# Sheet7.net
KiCad netlist of a schematic drawn in Altium Designer
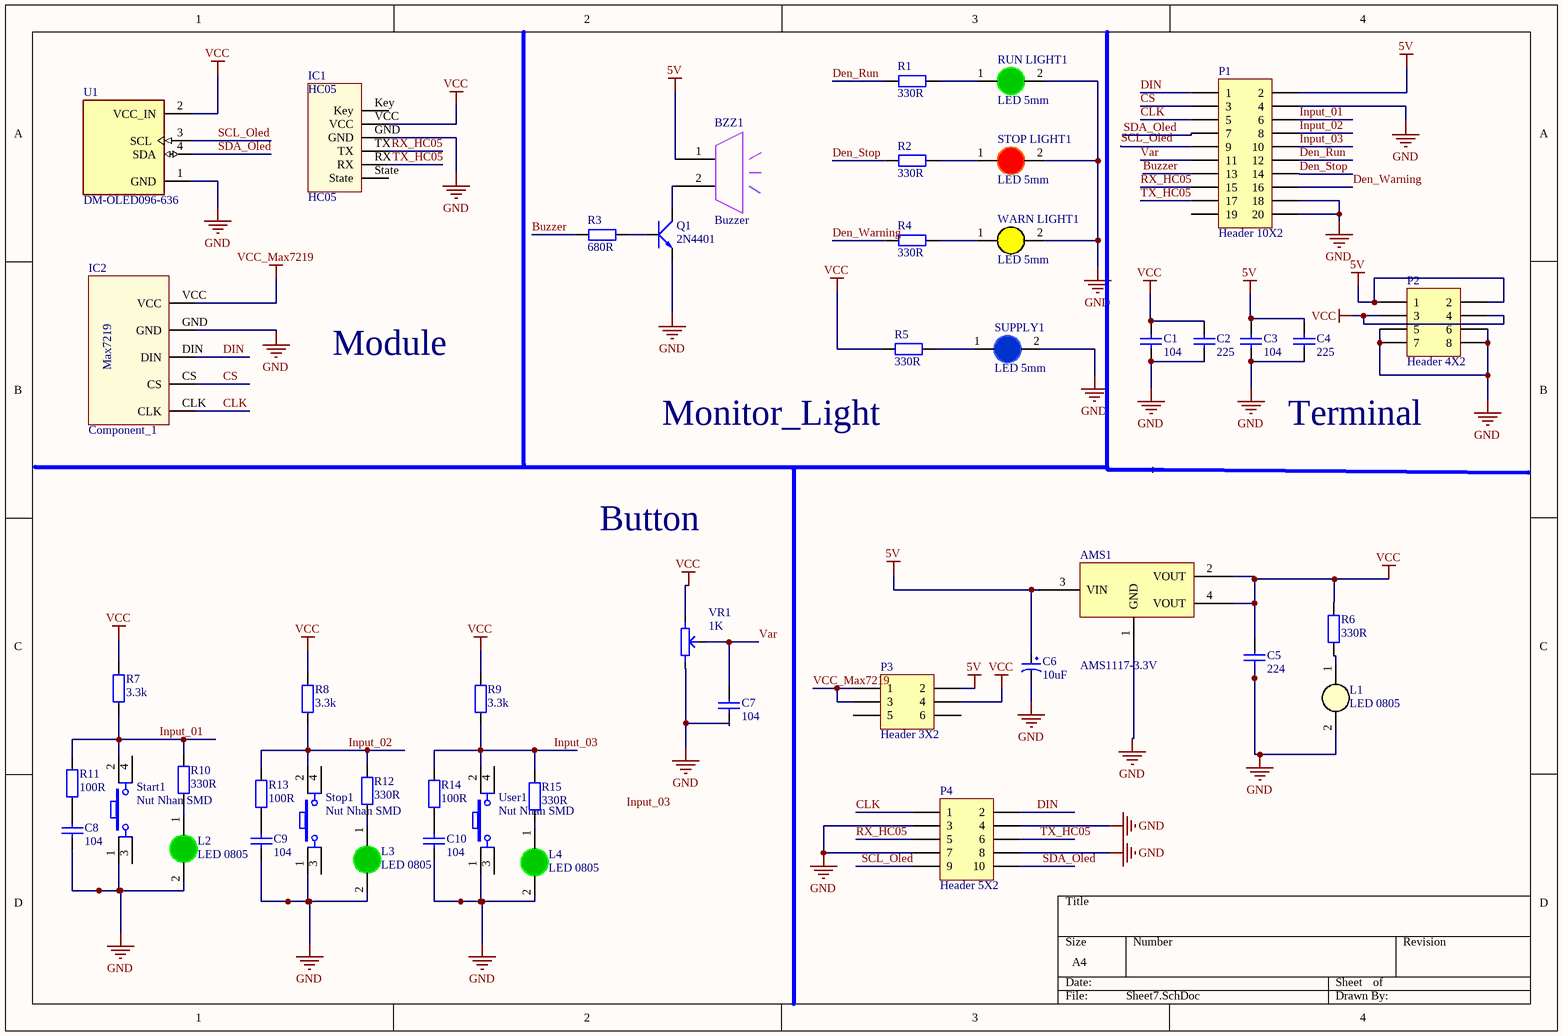
[diagram p0: Sheet7.SchDoc]

(export (version "E")
  (design (tool "Eeschema 10.0.6"))
  (components
    (comp (ref "AMS1")
      (value "AMS1117-3.3V")
      (footprint "SOT223")
      (description "Dán")
      (libsource (lib "Altium_Lib_by_KhueNguyenCreator") (part "AMS1117 SMD"))
    )
    (comp (ref "BZZ1")
      (value "Buzzer")
      (footprint "BUZZER_CT-1205-SMT")
      (libsource (lib "My library altium") (part "Buzzer"))
    )
    (comp (ref "C1")
      (value "104")
      (footprint "tu 0805")
      (description "Dán")
      (libsource (lib "Altium_Lib_by_KhueNguyenCreator") (part "Tu 0805 104 50V 10%"))
    )
    (comp (ref "C2")
      (value "225")
      (footprint "tu 0805")
      (description "Dán")
      (libsource (lib "Altium_Lib_by_KhueNguyenCreator") (part "Tu 0805 225 25V 10%"))
    )
    (comp (ref "C3")
      (value "104")
      (footprint "tu 0805")
      (description "Dán")
      (libsource (lib "Altium_Lib_by_KhueNguyenCreator") (part "Tu 0805 104 50V 10%"))
    )
    (comp (ref "C4")
      (value "225")
      (footprint "tu 0805")
      (description "Dán")
      (libsource (lib "Altium_Lib_by_KhueNguyenCreator") (part "Tu 0805 225 25V 10%"))
    )
    (comp (ref "C5")
      (value "224")
      (footprint "tu 0805")
      (description "Dán")
      (libsource (lib "Altium_Lib_by_KhueNguyenCreator") (part "Tu 0805 224 50V 10%"))
    )
    (comp (ref "C6")
      (value "10uF")
      (footprint "tu hoa 4mm")
      (description "Cắm")
      (libsource (lib "Altium_Lib_by_KhueNguyenCreator") (part "Tu Hoa 10uF 25V 4x7"))
    )
    (comp (ref "C7")
      (value "104")
      (footprint "tu 0805")
      (description "Dán")
      (libsource (lib "Altium_Lib_by_KhueNguyenCreator") (part "Tu 0805 104 50V 10%"))
    )
    (comp (ref "C8")
      (value "104")
      (footprint "tu 0805")
      (description "Dán")
      (libsource (lib "Altium_Lib_by_KhueNguyenCreator") (part "Tu 0805 104 50V 10%"))
    )
    (comp (ref "C9")
      (value "104")
      (footprint "tu 0805")
      (description "Dán")
      (libsource (lib "Altium_Lib_by_KhueNguyenCreator") (part "Tu 0805 104 50V 10%"))
    )
    (comp (ref "C10")
      (value "104")
      (footprint "tu 0805")
      (description "Dán")
      (libsource (lib "Altium_Lib_by_KhueNguyenCreator") (part "Tu 0805 104 50V 10%"))
    )
    (comp (ref "IC1") (value "HC05") (footprint "HC05") (libsource (lib "Thu_vien_KA_01") (part "HC05")))
    (comp (ref "IC2")
      (value "Component_1")
      (footprint "PCBComponent_1")
      (description "Max 7219 7 segment")
      (libsource (lib "Schlib1") (part "Component_1"))
    )
    (comp (ref "L1")
      (value "LED 0805")
      (footprint "LED-0805-Yellow")
      (description "Dán")
      (libsource (lib "Altium_Lib_by_KhueNguyenCreator") (part "LED 0805 Trang"))
    )
    (comp (ref "L2")
      (value "LED 0805")
      (footprint "LED-0805-Green")
      (description "Dán")
      (libsource (lib "Altium_Lib_by_KhueNguyenCreator") (part "LED 0805 Xanh La"))
    )
    (comp (ref "L3")
      (value "LED 0805")
      (footprint "LED-0805-Green")
      (description "Dán")
      (libsource (lib "Altium_Lib_by_KhueNguyenCreator") (part "LED 0805 Xanh La"))
    )
    (comp (ref "L4")
      (value "LED 0805")
      (footprint "LED-0805-Green")
      (description "Dán")
      (libsource (lib "Altium_Lib_by_KhueNguyenCreator") (part "LED 0805 Xanh La"))
    )
    (comp (ref "P1")
      (value "Header 10X2")
      (footprint "HDR2X10")
      (description "Header, 10-Pin, Dual row")
      (fields (field (name "PUBLISHER") "Altium Limited"))
      (libsource (lib "Miscellaneous Connectors") (part "Header 10X2"))
    )
    (comp (ref "P2")
      (value "Header 4X2")
      (footprint "HDR2X4")
      (description "Header, 4-Pin, Dual row")
      (fields (field (name "PUBLISHER") "Altium Limited"))
      (libsource (lib "My library altium") (part "Header 4X2"))
    )
    (comp (ref "P3")
      (value "Header 3X2")
      (footprint "HDR2X3")
      (description "Header, 3-Pin, Dual row")
      (fields (field (name "PUBLISHER") "Altium Limited"))
      (libsource (lib "My library altium") (part "Header 3X2"))
    )
    (comp (ref "P4")
      (value "Header 5X2")
      (footprint "HDR2X5")
      (description "Header, 5-Pin, Dual row")
      (fields (field (name "PUBLISHER") "Altium Limited"))
      (libsource (lib "My library altium") (part "Header 5X2"))
    )
    (comp (ref "Q1")
      (value "2N4401")
      (footprint "TO92")
      (description "NPN transistor")
      (libsource (lib "Altium_Lib_by_KhueNguyenCreator") (part "Trans C1815 DIP"))
    )
    (comp (ref "R1")
      (value "330R")
      (footprint "Tro SMD 0805")
      (description "Dán")
      (libsource (lib "Altium_Lib_by_KhueNguyenCreator") (part "Tro 0805 5% 330R"))
    )
    (comp (ref "R2")
      (value "330R")
      (footprint "Tro SMD 0805")
      (description "Dán")
      (libsource (lib "Altium_Lib_by_KhueNguyenCreator") (part "Tro 0805 5% 330R"))
    )
    (comp (ref "R3")
      (value "680R")
      (footprint "tro smd 0805")
      (description "Dán")
      (libsource (lib "Altium_Lib_by_KhueNguyenCreator") (part "Tro 0805 1% 680R"))
    )
    (comp (ref "R4")
      (value "330R")
      (footprint "Tro SMD 0805")
      (description "Dán")
      (libsource (lib "Altium_Lib_by_KhueNguyenCreator") (part "Tro 0805 5% 330R"))
    )
    (comp (ref "R5")
      (value "330R")
      (footprint "Tro SMD 0805")
      (description "Dán")
      (libsource (lib "Altium_Lib_by_KhueNguyenCreator") (part "Tro 0805 5% 330R"))
    )
    (comp (ref "R6")
      (value "330R")
      (footprint "Tro SMD 0805")
      (description "Dán")
      (libsource (lib "Altium_Lib_by_KhueNguyenCreator") (part "Tro 0805 5% 330R"))
    )
    (comp (ref "R7")
      (value "3.3k")
      (footprint "tro smd 0805")
      (description "Dán")
      (libsource (lib "Altium_Lib_by_KhueNguyenCreator") (part "Tro 0805 5% 3.3k"))
    )
    (comp (ref "R8")
      (value "3.3k")
      (footprint "tro smd 0805")
      (description "Dán")
      (libsource (lib "Altium_Lib_by_KhueNguyenCreator") (part "Tro 0805 5% 3.3k"))
    )
    (comp (ref "R9")
      (value "3.3k")
      (footprint "tro smd 0805")
      (description "Dán")
      (libsource (lib "Altium_Lib_by_KhueNguyenCreator") (part "Tro 0805 5% 3.3k"))
    )
    (comp (ref "R10")
      (value "330R")
      (footprint "Tro SMD 0805")
      (description "Dán")
      (libsource (lib "Altium_Lib_by_KhueNguyenCreator") (part "Tro 0805 5% 330R"))
    )
    (comp (ref "R11")
      (value "100R")
      (footprint "tro smd 0805")
      (description "Dán")
      (libsource (lib "Altium_Lib_by_KhueNguyenCreator") (part "Tro 0805 5% 100R"))
    )
    (comp (ref "R12")
      (value "330R")
      (footprint "Tro SMD 0805")
      (description "Dán")
      (libsource (lib "Altium_Lib_by_KhueNguyenCreator") (part "Tro 0805 5% 330R"))
    )
    (comp (ref "R13")
      (value "100R")
      (footprint "tro smd 0805")
      (description "Dán")
      (libsource (lib "Altium_Lib_by_KhueNguyenCreator") (part "Tro 0805 5% 100R"))
    )
    (comp (ref "R14")
      (value "100R")
      (footprint "tro smd 0805")
      (description "Dán")
      (libsource (lib "Altium_Lib_by_KhueNguyenCreator") (part "Tro 0805 5% 100R"))
    )
    (comp (ref "R15")
      (value "330R")
      (footprint "Tro SMD 0805")
      (description "Dán")
      (libsource (lib "Altium_Lib_by_KhueNguyenCreator") (part "Tro 0805 5% 330R"))
    )
    (comp (ref "RUN LIGHT1")
      (value "LED 5mm")
      (footprint "LED-5MM-Green")
      (description "Cắm")
      (libsource (lib "Altium_Lib_by_KhueNguyenCreator") (part "LED 5mm Xanh La"))
    )
    (comp (ref "Start1")
      (value "Nut Nhan SMD")
      (footprint "Nut Nhan 4 Chan SMD 6x6")
      (description "Nut Nhan 4 Chan 6.2x6.2x3.5")
      (libsource (lib "Altium_Lib_by_KhueNguyenCreator") (part "Nut Nhan 4 Chan SMD 6x6"))
    )
    (comp (ref "STOP LIGHT1")
      (value "LED 5mm")
      (footprint "LED-5MM-RED")
      (description "Cắm")
      (libsource (lib "Altium_Lib_by_KhueNguyenCreator") (part "LED 5mm Do"))
    )
    (comp (ref "Stop1")
      (value "Nut Nhan SMD")
      (footprint "Nut Nhan 4 Chan SMD 6x6")
      (description "Nut Nhan 4 Chan 6.2x6.2x3.5")
      (libsource (lib "Altium_Lib_by_KhueNguyenCreator") (part "Nut Nhan 4 Chan SMD 6x6"))
    )
    (comp (ref "SUPPLY1")
      (value "LED 5mm")
      (footprint "LED-5MM-BLUE")
      (description "Cắm")
      (libsource (lib "Altium_Lib_by_KhueNguyenCreator") (part "LED 5mm Xanh Duong"))
    )
    (comp (ref "U1")
      (value "DM-OLED096-636")
      (footprint "MODULE_DM-OLED096-636")
      (description "0.96â€ 128 X 64 MONOCHROME GRAPHIC OLED DISPLAY MODULE - I2C")
      (fields (field (name "MF") "Display Module"))
      (libsource (lib "DM-OLED096-636") (part "DM-OLED096-636"))
    )
    (comp (ref "User1")
      (value "Nut Nhan SMD")
      (footprint "Nut Nhan 4 Chan SMD 6x6")
      (description "Nut Nhan 4 Chan 6.2x6.2x3.5")
      (libsource (lib "Altium_Lib_by_KhueNguyenCreator") (part "Nut Nhan 4 Chan SMD 6x6"))
    )
    (comp (ref "VR1")
      (value "1K")
      (footprint "Bien Tro Tam Giac Dung")
      (description "Cắm")
      (libsource (lib "Altium_Lib_by_KhueNguyenCreator") (part "Bien tro tam giac 1K Dung"))
    )
    (comp (ref "WARN LIGHT1")
      (value "LED 5mm")
      (footprint "LED-5MM-Yellow")
      (description "Cắm")
      (libsource (lib "Altium_Lib_by_KhueNguyenCreator") (part "LED 5mm Vang"))
    )
  )
  (nets
    (net (code "1") (name "/Buzzer") (class "Default")
      (node (ref "P1") (pin "13") (pinfunction "13_13") (pintype "passive"))
      (node (ref "R3") (pin "1") (pinfunction "1_1") (pintype "passive"))
    )
    (net (code "2") (name "/CLK") (class "Default")
      (node (ref "IC2") (pin "CLK") (pinfunction "CLK_CLK") (pintype "passive"))
      (node (ref "P1") (pin "5") (pinfunction "5_5") (pintype "passive"))
      (node (ref "P4") (pin "1") (pinfunction "1_1") (pintype "passive"))
    )
    (net (code "3") (name "/CS") (class "Default")
      (node (ref "IC2") (pin "CS") (pinfunction "CS_CS") (pintype "passive"))
      (node (ref "P1") (pin "3") (pinfunction "3_3") (pintype "passive"))
    )
    (net (code "4") (name "/DIN") (class "Default")
      (node (ref "IC2") (pin "DIN") (pinfunction "DIN_DIN") (pintype "passive"))
      (node (ref "P1") (pin "1") (pinfunction "1_1") (pintype "passive"))
      (node (ref "P4") (pin "2") (pinfunction "2_2") (pintype "passive"))
    )
    (net (code "5") (name "/Den_Run") (class "Default")
      (node (ref "P1") (pin "12") (pinfunction "12_12") (pintype "passive"))
      (node (ref "R1") (pin "1") (pinfunction "1_1") (pintype "passive"))
    )
    (net (code "6") (name "/Den_Stop") (class "Default")
      (node (ref "P1") (pin "14") (pinfunction "14_14") (pintype "passive"))
      (node (ref "R2") (pin "1") (pinfunction "1_1") (pintype "passive"))
    )
    (net (code "7") (name "/Den_Warning") (class "Default")
      (node (ref "P1") (pin "16") (pinfunction "16_16") (pintype "passive"))
      (node (ref "R4") (pin "1") (pinfunction "1_1") (pintype "passive"))
    )
    (net (code "8") (name "/Input_01") (class "Default")
      (node (ref "P1") (pin "6") (pinfunction "6_6") (pintype "passive"))
      (node (ref "R10") (pin "1") (pinfunction "1_1") (pintype "passive"))
      (node (ref "R11") (pin "2") (pinfunction "2_2") (pintype "passive"))
      (node (ref "R7") (pin "1") (pinfunction "1_1") (pintype "passive"))
      (node (ref "Start1") (pin "2") (pintype "passive"))
    )
    (net (code "9") (name "/Input_02") (class "Default")
      (node (ref "P1") (pin "8") (pinfunction "8_8") (pintype "passive"))
      (node (ref "R12") (pin "1") (pinfunction "1_1") (pintype "passive"))
      (node (ref "R13") (pin "2") (pinfunction "2_2") (pintype "passive"))
      (node (ref "R8") (pin "1") (pinfunction "1_1") (pintype "passive"))
      (node (ref "Stop1") (pin "2") (pintype "passive"))
    )
    (net (code "10") (name "/Input_03") (class "Default")
      (node (ref "P1") (pin "10") (pinfunction "10_10") (pintype "passive"))
      (node (ref "R14") (pin "2") (pinfunction "2_2") (pintype "passive"))
      (node (ref "R15") (pin "1") (pinfunction "1_1") (pintype "passive"))
      (node (ref "R9") (pin "1") (pinfunction "1_1") (pintype "passive"))
      (node (ref "User1") (pin "2") (pintype "passive"))
    )
    (net (code "11") (name "/RX_HC05") (class "Default")
      (node (ref "IC1") (pin "TX") (pinfunction "TX_TX") (pintype "passive"))
      (node (ref "P1") (pin "15") (pinfunction "15_15") (pintype "passive"))
      (node (ref "P4") (pin "5") (pinfunction "5_5") (pintype "passive"))
    )
    (net (code "12") (name "/SCL_Oled") (class "Default")
      (node (ref "P1") (pin "9") (pinfunction "9_9") (pintype "passive"))
      (node (ref "P4") (pin "9") (pinfunction "9_9") (pintype "passive"))
      (node (ref "U1") (pin "3") (pinfunction "SCL_3") (pintype "input"))
    )
    (net (code "13") (name "/SDA_Oled") (class "Default")
      (node (ref "P1") (pin "7") (pinfunction "7_7") (pintype "passive"))
      (node (ref "P4") (pin "10") (pinfunction "10_10") (pintype "passive"))
      (node (ref "U1") (pin "4") (pinfunction "SDA_4") (pintype "bidirectional"))
    )
    (net (code "14") (name "/TX_HC05") (class "Default")
      (node (ref "IC1") (pin "RX") (pinfunction "RX_RX") (pintype "passive"))
      (node (ref "P1") (pin "17") (pinfunction "17_17") (pintype "passive"))
      (node (ref "P4") (pin "6") (pinfunction "6_6") (pintype "passive"))
    )
    (net (code "15") (name "/Var") (class "Default")
      (node (ref "C7") (pin "1") (pinfunction "1_1") (pintype "passive"))
      (node (ref "P1") (pin "11") (pinfunction "11_11") (pintype "passive"))
      (node (ref "VR1") (pin "2") (pinfunction "2_2") (pintype "passive"))
    )
    (net (code "16") (name "5V") (class "Default")
      (node (ref "AMS1") (pin "3") (pinfunction "VIN_3") (pintype "passive"))
      (node (ref "BZZ1") (pin "1") (pinfunction "1_1") (pintype "passive"))
      (node (ref "C3") (pin "1") (pinfunction "1_1") (pintype "passive"))
      (node (ref "C4") (pin "1") (pinfunction "1_1") (pintype "passive"))
      (node (ref "C6") (pin "1") (pinfunction "1_1") (pintype "passive"))
      (node (ref "P1") (pin "2") (pinfunction "2_2") (pintype "passive"))
      (node (ref "P2") (pin "1") (pinfunction "1_1") (pintype "passive"))
      (node (ref "P2") (pin "2") (pinfunction "2_2") (pintype "passive"))
      (node (ref "P3") (pin "2") (pinfunction "2_2") (pintype "passive"))
    )
    (net (code "17") (name "GND") (class "Default")
      (node (ref "AMS1") (pin "1") (pinfunction "GND_1") (pintype "passive"))
      (node (ref "C1") (pin "2") (pinfunction "2_2") (pintype "passive"))
      (node (ref "C10") (pin "2") (pinfunction "2_2") (pintype "passive"))
      (node (ref "C2") (pin "2") (pinfunction "2_2") (pintype "passive"))
      (node (ref "C3") (pin "2") (pinfunction "2_2") (pintype "passive"))
      (node (ref "C4") (pin "2") (pinfunction "2_2") (pintype "passive"))
      (node (ref "C5") (pin "2") (pinfunction "2_2") (pintype "passive"))
      (node (ref "C6") (pin "2") (pinfunction "2_2") (pintype "passive"))
      (node (ref "C7") (pin "2") (pinfunction "2_2") (pintype "passive"))
      (node (ref "C8") (pin "2") (pinfunction "2_2") (pintype "passive"))
      (node (ref "C9") (pin "2") (pinfunction "2_2") (pintype "passive"))
      (node (ref "IC1") (pin "GND") (pinfunction "GND_GND") (pintype "passive"))
      (node (ref "IC2") (pin "GND") (pinfunction "GND_GND") (pintype "passive"))
      (node (ref "L1") (pin "2") (pinfunction "K_2") (pintype "passive"))
      (node (ref "L2") (pin "2") (pinfunction "K_2") (pintype "passive"))
      (node (ref "L3") (pin "2") (pinfunction "K_2") (pintype "passive"))
      (node (ref "L4") (pin "2") (pinfunction "K_2") (pintype "passive"))
      (node (ref "P1") (pin "18") (pinfunction "18_18") (pintype "passive"))
      (node (ref "P1") (pin "20") (pinfunction "20_20") (pintype "passive"))
      (node (ref "P1") (pin "4") (pinfunction "4_4") (pintype "passive"))
      (node (ref "P2") (pin "5") (pinfunction "5_5") (pintype "passive"))
      (node (ref "P2") (pin "6") (pinfunction "6_6") (pintype "passive"))
      (node (ref "P2") (pin "7") (pinfunction "7_7") (pintype "passive"))
      (node (ref "P2") (pin "8") (pinfunction "8_8") (pintype "passive"))
      (node (ref "P4") (pin "3") (pinfunction "3_3") (pintype "passive"))
      (node (ref "P4") (pin "4") (pinfunction "4_4") (pintype "passive"))
      (node (ref "P4") (pin "7") (pinfunction "7_7") (pintype "passive"))
      (node (ref "P4") (pin "8") (pinfunction "8_8") (pintype "passive"))
      (node (ref "Q1") (pin "1") (pinfunction "E_1") (pintype "passive"))
      (node (ref "RUN LIGHT1") (pin "2") (pinfunction "K_2") (pintype "passive"))
      (node (ref "STOP LIGHT1") (pin "2") (pinfunction "K_2") (pintype "passive"))
      (node (ref "SUPPLY1") (pin "2") (pinfunction "K_2") (pintype "passive"))
      (node (ref "Start1") (pin "1") (pintype "passive"))
      (node (ref "Stop1") (pin "1") (pintype "passive"))
      (node (ref "U1") (pin "1") (pinfunction "GND_1") (pintype "power_in"))
      (node (ref "User1") (pin "1") (pintype "passive"))
      (node (ref "VR1") (pin "3") (pinfunction "3_3") (pintype "passive"))
      (node (ref "WARN LIGHT1") (pin "2") (pinfunction "K_2") (pintype "passive"))
    )
    (net (code "18") (name "Net-(C8-Pad1)") (class "Default")
      (node (ref "C8") (pin "1") (pinfunction "1_1") (pintype "passive"))
      (node (ref "R11") (pin "1") (pinfunction "1_1") (pintype "passive"))
    )
    (net (code "19") (name "Net-(C9-Pad1)") (class "Default")
      (node (ref "C9") (pin "1") (pinfunction "1_1") (pintype "passive"))
      (node (ref "R13") (pin "1") (pinfunction "1_1") (pintype "passive"))
    )
    (net (code "20") (name "Net-(C10-Pad1)") (class "Default")
      (node (ref "C10") (pin "1") (pinfunction "1_1") (pintype "passive"))
      (node (ref "R14") (pin "1") (pinfunction "1_1") (pintype "passive"))
    )
    (net (code "21") (name "Net-(L1-A)") (class "Default")
      (node (ref "L1") (pin "1") (pinfunction "A_1") (pintype "passive"))
      (node (ref "R6") (pin "1") (pinfunction "1_1") (pintype "passive"))
    )
    (net (code "22") (name "Net-(L2-A)") (class "Default")
      (node (ref "L2") (pin "1") (pinfunction "A_1") (pintype "passive"))
      (node (ref "R10") (pin "2") (pinfunction "2_2") (pintype "passive"))
    )
    (net (code "23") (name "Net-(L3-A)") (class "Default")
      (node (ref "L3") (pin "1") (pinfunction "A_1") (pintype "passive"))
      (node (ref "R12") (pin "2") (pinfunction "2_2") (pintype "passive"))
    )
    (net (code "24") (name "Net-(L4-A)") (class "Default")
      (node (ref "L4") (pin "1") (pinfunction "A_1") (pintype "passive"))
      (node (ref "R15") (pin "2") (pinfunction "2_2") (pintype "passive"))
    )
    (net (code "25") (name "Net-(Q1-B)") (class "Default")
      (node (ref "Q1") (pin "3") (pinfunction "B_3") (pintype "passive"))
      (node (ref "R3") (pin "2") (pinfunction "2_2") (pintype "passive"))
    )
    (net (code "26") (name "Net-(Q1-C)") (class "Default")
      (node (ref "BZZ1") (pin "2") (pinfunction "2_2") (pintype "passive"))
      (node (ref "Q1") (pin "2") (pinfunction "C_2") (pintype "passive"))
    )
    (net (code "27") (name "Net-(RUN LIGHT1-A)") (class "Default")
      (node (ref "R1") (pin "2") (pinfunction "2_2") (pintype "passive"))
      (node (ref "RUN LIGHT1") (pin "1") (pinfunction "A_1") (pintype "passive"))
    )
    (net (code "28") (name "Net-(STOP LIGHT1-A)") (class "Default")
      (node (ref "R2") (pin "2") (pinfunction "2_2") (pintype "passive"))
      (node (ref "STOP LIGHT1") (pin "1") (pinfunction "A_1") (pintype "passive"))
    )
    (net (code "29") (name "Net-(SUPPLY1-A)") (class "Default")
      (node (ref "R5") (pin "2") (pinfunction "2_2") (pintype "passive"))
      (node (ref "SUPPLY1") (pin "1") (pinfunction "A_1") (pintype "passive"))
    )
    (net (code "30") (name "Net-(WARN LIGHT1-A)") (class "Default")
      (node (ref "R4") (pin "2") (pinfunction "2_2") (pintype "passive"))
      (node (ref "WARN LIGHT1") (pin "1") (pinfunction "A_1") (pintype "passive"))
    )
    (net (code "31") (name "VCC") (class "Default")
      (node (ref "AMS1") (pin "2") (pinfunction "VOUT_2") (pintype "passive"))
      (node (ref "AMS1") (pin "4") (pinfunction "VOUT_4") (pintype "passive"))
      (node (ref "C1") (pin "1") (pinfunction "1_1") (pintype "passive"))
      (node (ref "C2") (pin "1") (pinfunction "1_1") (pintype "passive"))
      (node (ref "C5") (pin "1") (pinfunction "1_1") (pintype "passive"))
      (node (ref "IC1") (pin "VCC") (pinfunction "VCC_VCC") (pintype "passive"))
      (node (ref "P2") (pin "3") (pinfunction "3_3") (pintype "passive"))
      (node (ref "P2") (pin "4") (pinfunction "4_4") (pintype "passive"))
      (node (ref "P3") (pin "4") (pinfunction "4_4") (pintype "passive"))
      (node (ref "R5") (pin "1") (pinfunction "1_1") (pintype "passive"))
      (node (ref "R6") (pin "2") (pinfunction "2_2") (pintype "passive"))
      (node (ref "R7") (pin "2") (pinfunction "2_2") (pintype "passive"))
      (node (ref "R8") (pin "2") (pinfunction "2_2") (pintype "passive"))
      (node (ref "R9") (pin "2") (pinfunction "2_2") (pintype "passive"))
      (node (ref "U1") (pin "2") (pinfunction "VCC_IN_2") (pintype "power_in"))
      (node (ref "VR1") (pin "1") (pinfunction "1_1") (pintype "passive"))
    )
    (net (code "32") (name "VCC_Max7219") (class "Default")
      (node (ref "IC2") (pin "VCC") (pinfunction "VCC_VCC") (pintype "passive"))
      (node (ref "P3") (pin "1") (pinfunction "1_1") (pintype "passive"))
      (node (ref "P3") (pin "3") (pinfunction "3_3") (pintype "passive"))
    )
    (net (code "33") (name "unconnected-(IC1-PadKey)") (class "Default")
      (node (ref "IC1") (pin "Key") (pinfunction "Key_Key") (pintype "passive"))
    )
    (net (code "34") (name "unconnected-(IC1-PadState)") (class "Default")
      (node (ref "IC1") (pin "State") (pinfunction "State_State") (pintype "passive"))
    )
    (net (code "35") (name "unconnected-(P1-Pad19)") (class "Default")
      (node (ref "P1") (pin "19") (pinfunction "19_19") (pintype "passive"))
    )
    (net (code "36") (name "unconnected-(P3-Pad5)") (class "Default")
      (node (ref "P3") (pin "5") (pinfunction "5_5") (pintype "passive"))
    )
    (net (code "37") (name "unconnected-(P3-Pad6)") (class "Default")
      (node (ref "P3") (pin "6") (pinfunction "6_6") (pintype "passive"))
    )
    (net (code "38") (name "unconnected-(Start1-Pad3)") (class "Default")
      (node (ref "Start1") (pin "3") (pintype "passive"))
    )
    (net (code "39") (name "unconnected-(Start1-Pad4)") (class "Default")
      (node (ref "Start1") (pin "4") (pintype "passive"))
    )
    (net (code "40") (name "unconnected-(Stop1-Pad3)") (class "Default")
      (node (ref "Stop1") (pin "3") (pintype "passive"))
    )
    (net (code "41") (name "unconnected-(Stop1-Pad4)") (class "Default")
      (node (ref "Stop1") (pin "4") (pintype "passive"))
    )
    (net (code "42") (name "unconnected-(User1-Pad3)") (class "Default")
      (node (ref "User1") (pin "3") (pintype "passive"))
    )
    (net (code "43") (name "unconnected-(User1-Pad4)") (class "Default")
      (node (ref "User1") (pin "4") (pintype "passive"))
    )
  )
)
